# 8steps.net
KiCad netlist of a schematic drawn in EAGLE
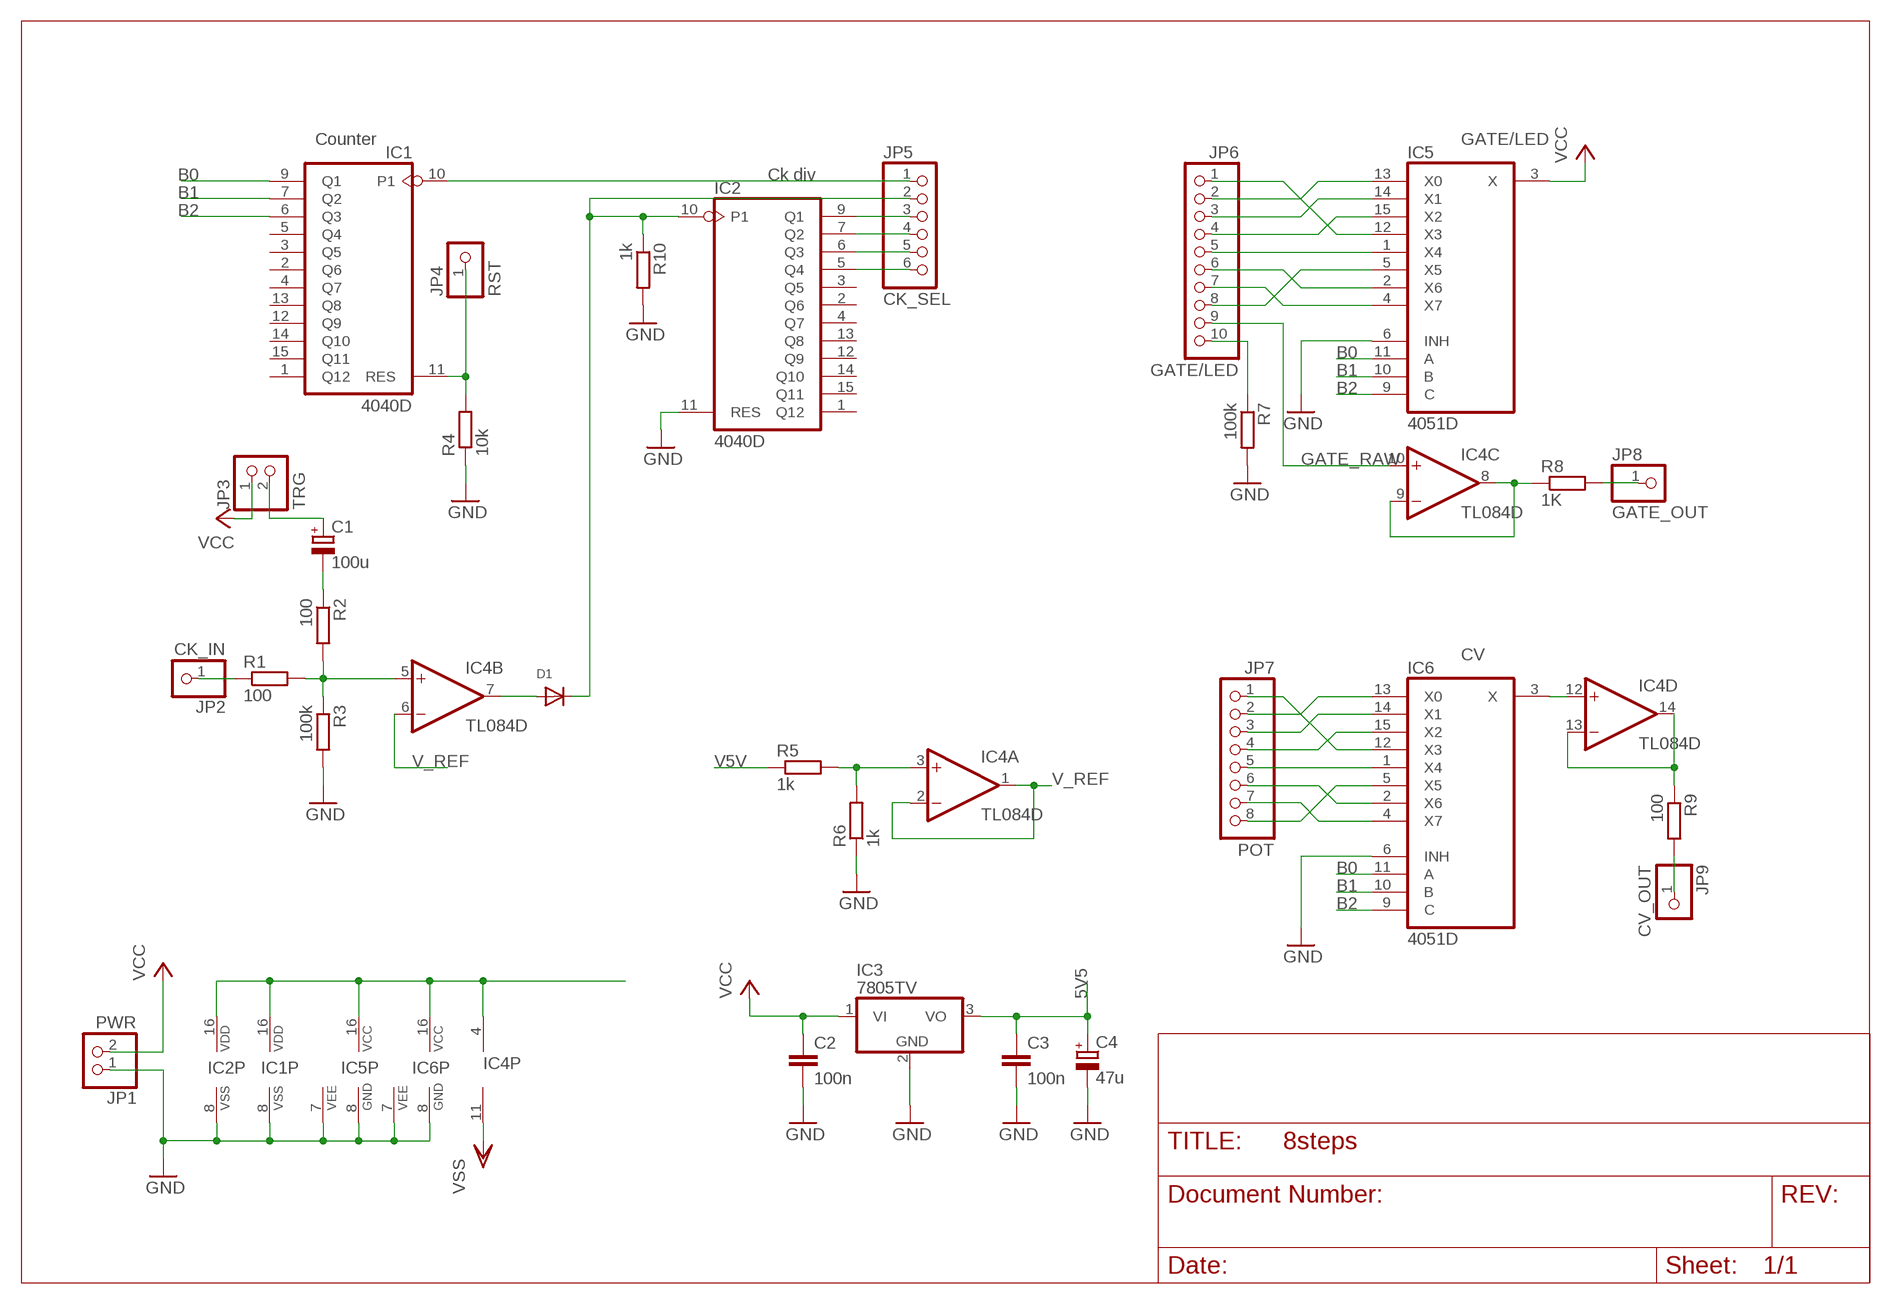
[diagram p0: schematic, sheet 1]

(export (version "E")
  (design (tool "Eeschema 10.0.6"))
  (components
    (comp (ref "C1")
      (value "100u")
      (footprint "eagle-import:E2,5-7")
      (libsource (lib "eagle-import") (part "CPOL-EUE2.5-7"))
    )
    (comp (ref "C2")
      (value "100n")
      (footprint "eagle-import:C050-025X075")
      (libsource (lib "eagle-import") (part "C-EU050-025X075"))
    )
    (comp (ref "C3")
      (value "100n")
      (footprint "eagle-import:C050-025X075")
      (libsource (lib "eagle-import") (part "C-EU050-025X075"))
    )
    (comp (ref "C4")
      (value "47u")
      (footprint "eagle-import:E2,5-7")
      (libsource (lib "eagle-import") (part "CPOL-EUE2.5-7"))
    )
    (comp (ref "D1")
      (value "DIODESOT23_WAVE")
      (footprint "eagle-import:SOT23-W")
      (libsource (lib "eagle-import") (part "DIODESOT23_WAVE"))
    )
    (comp (ref "IC1")
      (value "4040D")
      (footprint "eagle-import:SO16")
      (libsource (lib "eagle-import") (part "4040D"))
    )
    (comp (ref "IC2")
      (value "4040D")
      (footprint "eagle-import:SO16")
      (libsource (lib "eagle-import") (part "4040D"))
    )
    (comp (ref "IC3")
      (value "7805TV")
      (footprint "eagle-import:TO220V")
      (libsource (lib "eagle-import") (part "78TV05"))
    )
    (comp (ref "IC4")
      (value "TL084D")
      (footprint "eagle-import:SO14")
      (libsource (lib "eagle-import") (part "TL084D"))
    )
    (comp (ref "IC5")
      (value "4051D")
      (footprint "eagle-import:SO16")
      (libsource (lib "eagle-import") (part "4051D"))
    )
    (comp (ref "IC6")
      (value "4051D")
      (footprint "eagle-import:SO16")
      (libsource (lib "eagle-import") (part "4051D"))
    )
    (comp (ref "JP1")
      (value "PWR")
      (footprint "eagle-import:1X02")
      (libsource (lib "eagle-import") (part "PINHD-1X2"))
    )
    (comp (ref "JP2")
      (value "CK_IN")
      (footprint "eagle-import:1X01")
      (libsource (lib "eagle-import") (part "PINHD-1X1"))
    )
    (comp (ref "JP3")
      (value "TRG")
      (footprint "eagle-import:1X02")
      (libsource (lib "eagle-import") (part "PINHD-1X2"))
    )
    (comp (ref "JP4")
      (value "RST")
      (footprint "eagle-import:1X01")
      (libsource (lib "eagle-import") (part "PINHD-1X1"))
    )
    (comp (ref "JP5")
      (value "CK_SEL")
      (footprint "eagle-import:1X06")
      (libsource (lib "eagle-import") (part "PINHD-1X6"))
    )
    (comp (ref "JP6")
      (value "GATE/LED")
      (footprint "eagle-import:1X10")
      (libsource (lib "eagle-import") (part "PINHD-1X10"))
    )
    (comp (ref "JP7")
      (value "POT")
      (footprint "eagle-import:1X08")
      (libsource (lib "eagle-import") (part "PINHD-1X8"))
    )
    (comp (ref "JP8")
      (value "GATE_OUT")
      (footprint "eagle-import:1X01")
      (libsource (lib "eagle-import") (part "PINHD-1X1"))
    )
    (comp (ref "JP9")
      (value "CV_OUT")
      (footprint "eagle-import:1X01")
      (libsource (lib "eagle-import") (part "PINHD-1X1"))
    )
    (comp (ref "R1")
      (value "100")
      (footprint "eagle-import:R0805")
      (libsource (lib "eagle-import") (part "R-EU_R0805"))
    )
    (comp (ref "R2")
      (value "100")
      (footprint "eagle-import:R0805")
      (libsource (lib "eagle-import") (part "R-EU_R0805"))
    )
    (comp (ref "R3")
      (value "100k")
      (footprint "eagle-import:R0805")
      (libsource (lib "eagle-import") (part "R-EU_R0805"))
    )
    (comp (ref "R4")
      (value "10k")
      (footprint "eagle-import:R0805")
      (libsource (lib "eagle-import") (part "R-EU_R0805"))
    )
    (comp (ref "R5")
      (value "1k")
      (footprint "eagle-import:R0805")
      (libsource (lib "eagle-import") (part "R-EU_R0805"))
    )
    (comp (ref "R6")
      (value "1k")
      (footprint "eagle-import:R0805")
      (libsource (lib "eagle-import") (part "R-EU_R0805"))
    )
    (comp (ref "R7")
      (value "100k")
      (footprint "eagle-import:R0805")
      (libsource (lib "eagle-import") (part "R-EU_R0805"))
    )
    (comp (ref "R8")
      (value "1K")
      (footprint "eagle-import:R0805")
      (libsource (lib "eagle-import") (part "R-EU_R0805"))
    )
    (comp (ref "R9")
      (value "100")
      (footprint "eagle-import:R0805")
      (libsource (lib "eagle-import") (part "R-EU_R0805"))
    )
    (comp (ref "R10")
      (value "1k")
      (footprint "eagle-import:R0805")
      (libsource (lib "eagle-import") (part "R-EU_R0805"))
    )
  )
  (nets
    (net (code "1") (name "/5V5") (class "Default")
      (node (ref "C3") (pin "1") (pinfunction "1_1") (pintype "passive"))
      (node (ref "C4") (pin "+") (pinfunction "+_+") (pintype "passive"))
      (node (ref "IC3") (pin "3") (pinfunction "VO_3") (pintype "passive"))
    )
    (net (code "2") (name "/B0") (class "Default")
      (node (ref "IC1") (pin "9") (pinfunction "Q1_9") (pintype "output"))
      (node (ref "IC5") (pin "11") (pinfunction "A_11") (pintype "input"))
      (node (ref "IC6") (pin "11") (pinfunction "A_11") (pintype "input"))
    )
    (net (code "3") (name "/B1") (class "Default")
      (node (ref "IC1") (pin "7") (pinfunction "Q2_7") (pintype "output"))
      (node (ref "IC5") (pin "10") (pinfunction "B_10") (pintype "input"))
      (node (ref "IC6") (pin "10") (pinfunction "B_10") (pintype "input"))
    )
    (net (code "4") (name "/B2") (class "Default")
      (node (ref "IC1") (pin "6") (pinfunction "Q3_6") (pintype "output"))
      (node (ref "IC5") (pin "9") (pinfunction "C_9") (pintype "input"))
      (node (ref "IC6") (pin "9") (pinfunction "C_9") (pintype "input"))
    )
    (net (code "5") (name "/GATE_RAW") (class "Default")
      (node (ref "IC4") (pin "10") (pinfunction "+IN_10") (pintype "input"))
      (node (ref "JP6") (pin "9") (pinfunction "9_9") (pintype "passive"))
    )
    (net (code "6") (name "/V5V") (class "Default")
      (node (ref "IC1") (pin "16") (pinfunction "VDD_16") (pintype "power_in"))
      (node (ref "IC2") (pin "16") (pinfunction "VDD_16") (pintype "power_in"))
      (node (ref "IC4") (pin "4") (pinfunction "V+_4") (pintype "power_in"))
      (node (ref "IC5") (pin "16") (pinfunction "VCC_16") (pintype "power_in"))
      (node (ref "IC6") (pin "16") (pinfunction "VCC_16") (pintype "power_in"))
      (node (ref "R5") (pin "1") (pinfunction "1_1") (pintype "passive"))
    )
    (net (code "7") (name "/V_REF") (class "Default")
      (node (ref "IC4") (pin "1") (pinfunction "OUT_1") (pintype "output"))
      (node (ref "IC4") (pin "2") (pinfunction "-IN_2") (pintype "input"))
      (node (ref "IC4") (pin "6") (pinfunction "-IN_6") (pintype "input"))
    )
    (net (code "8") (name "GND") (class "Default")
      (node (ref "C2") (pin "2") (pinfunction "2_2") (pintype "passive"))
      (node (ref "C3") (pin "2") (pinfunction "2_2") (pintype "passive"))
      (node (ref "C4") (pin "-") (pinfunction "-_-") (pintype "passive"))
      (node (ref "IC1") (pin "8") (pinfunction "VSS_8") (pintype "power_in"))
      (node (ref "IC2") (pin "11") (pinfunction "RES_11") (pintype "input"))
      (node (ref "IC2") (pin "8") (pinfunction "VSS_8") (pintype "power_in"))
      (node (ref "IC3") (pin "2") (pinfunction "GND_2") (pintype "passive"))
      (node (ref "IC5") (pin "6") (pinfunction "INH_6") (pintype "input"))
      (node (ref "IC5") (pin "7") (pinfunction "VEE_7") (pintype "power_in"))
      (node (ref "IC5") (pin "8") (pinfunction "GND_8") (pintype "power_in"))
      (node (ref "IC6") (pin "6") (pinfunction "INH_6") (pintype "input"))
      (node (ref "IC6") (pin "7") (pinfunction "VEE_7") (pintype "power_in"))
      (node (ref "IC6") (pin "8") (pinfunction "GND_8") (pintype "power_in"))
      (node (ref "JP1") (pin "1") (pinfunction "1_1") (pintype "passive"))
      (node (ref "R10") (pin "2") (pinfunction "2_2") (pintype "passive"))
      (node (ref "R3") (pin "2") (pinfunction "2_2") (pintype "passive"))
      (node (ref "R4") (pin "1") (pinfunction "1_1") (pintype "passive"))
      (node (ref "R6") (pin "1") (pinfunction "1_1") (pintype "passive"))
      (node (ref "R7") (pin "2") (pinfunction "2_2") (pintype "passive"))
    )
    (net (code "9") (name "Net-(C1-Pad+)") (class "Default")
      (node (ref "C1") (pin "+") (pinfunction "+_+") (pintype "passive"))
      (node (ref "JP3") (pin "2") (pinfunction "2_2") (pintype "passive"))
    )
    (net (code "10") (name "Net-(C1-Pad-)") (class "Default")
      (node (ref "C1") (pin "-") (pinfunction "-_-") (pintype "passive"))
      (node (ref "R2") (pin "1") (pinfunction "1_1") (pintype "passive"))
    )
    (net (code "11") (name "Net-(D1-A)") (class "Default")
      (node (ref "D1") (pin "1") (pinfunction "A_1") (pintype "passive"))
      (node (ref "IC4") (pin "7") (pinfunction "OUT_7") (pintype "output"))
    )
    (net (code "12") (name "Net-(D1-C)") (class "Default")
      (node (ref "D1") (pin "3") (pinfunction "C_3") (pintype "passive"))
      (node (ref "IC2") (pin "10") (pinfunction "P1_10") (pintype "input"))
      (node (ref "JP5") (pin "2") (pinfunction "2_2") (pintype "passive"))
      (node (ref "R10") (pin "1") (pinfunction "1_1") (pintype "passive"))
    )
    (net (code "13") (name "Net-(IC1A-P1)") (class "Default")
      (node (ref "IC1") (pin "10") (pinfunction "P1_10") (pintype "input"))
      (node (ref "JP5") (pin "1") (pinfunction "1_1") (pintype "passive"))
    )
    (net (code "14") (name "Net-(IC1A-RES)") (class "Default")
      (node (ref "IC1") (pin "11") (pinfunction "RES_11") (pintype "input"))
      (node (ref "JP4") (pin "1") (pinfunction "1_1") (pintype "passive"))
      (node (ref "R4") (pin "2") (pinfunction "2_2") (pintype "passive"))
    )
    (net (code "15") (name "Net-(IC2A-Q1)") (class "Default")
      (node (ref "IC2") (pin "9") (pinfunction "Q1_9") (pintype "output"))
      (node (ref "JP5") (pin "3") (pinfunction "3_3") (pintype "passive"))
    )
    (net (code "16") (name "Net-(IC2A-Q2)") (class "Default")
      (node (ref "IC2") (pin "7") (pinfunction "Q2_7") (pintype "output"))
      (node (ref "JP5") (pin "4") (pinfunction "4_4") (pintype "passive"))
    )
    (net (code "17") (name "Net-(IC2A-Q3)") (class "Default")
      (node (ref "IC2") (pin "6") (pinfunction "Q3_6") (pintype "output"))
      (node (ref "JP5") (pin "5") (pinfunction "5_5") (pintype "passive"))
    )
    (net (code "18") (name "Net-(IC2A-Q4)") (class "Default")
      (node (ref "IC2") (pin "5") (pinfunction "Q4_5") (pintype "output"))
      (node (ref "JP5") (pin "6") (pinfunction "6_6") (pintype "passive"))
    )
    (net (code "19") (name "Net-(IC4A-+IN)") (class "Default")
      (node (ref "IC4") (pin "3") (pinfunction "+IN_3") (pintype "input"))
      (node (ref "R5") (pin "2") (pinfunction "2_2") (pintype "passive"))
      (node (ref "R6") (pin "2") (pinfunction "2_2") (pintype "passive"))
    )
    (net (code "20") (name "Net-(IC4B-+IN)") (class "Default")
      (node (ref "IC4") (pin "5") (pinfunction "+IN_5") (pintype "input"))
      (node (ref "R1") (pin "2") (pinfunction "2_2") (pintype "passive"))
      (node (ref "R2") (pin "2") (pinfunction "2_2") (pintype "passive"))
      (node (ref "R3") (pin "1") (pinfunction "1_1") (pintype "passive"))
    )
    (net (code "21") (name "Net-(IC4C--IN)") (class "Default")
      (node (ref "IC4") (pin "8") (pinfunction "OUT_8") (pintype "output"))
      (node (ref "IC4") (pin "9") (pinfunction "-IN_9") (pintype "input"))
      (node (ref "R8") (pin "1") (pinfunction "1_1") (pintype "passive"))
    )
    (net (code "22") (name "Net-(IC4D-+IN)") (class "Default")
      (node (ref "IC4") (pin "12") (pinfunction "+IN_12") (pintype "input"))
      (node (ref "IC6") (pin "3") (pinfunction "X_3") (pintype "bidirectional"))
    )
    (net (code "23") (name "Net-(IC4D--IN)") (class "Default")
      (node (ref "IC4") (pin "13") (pinfunction "-IN_13") (pintype "input"))
      (node (ref "IC4") (pin "14") (pinfunction "OUT_14") (pintype "output"))
      (node (ref "R9") (pin "1") (pinfunction "1_1") (pintype "passive"))
    )
    (net (code "24") (name "Net-(IC5A-X0)") (class "Default")
      (node (ref "IC5") (pin "13") (pinfunction "X0_13") (pintype "bidirectional"))
      (node (ref "JP6") (pin "2") (pinfunction "2_2") (pintype "passive"))
    )
    (net (code "25") (name "Net-(IC5A-X1)") (class "Default")
      (node (ref "IC5") (pin "14") (pinfunction "X1_14") (pintype "bidirectional"))
      (node (ref "JP6") (pin "3") (pinfunction "3_3") (pintype "passive"))
    )
    (net (code "26") (name "Net-(IC5A-X2)") (class "Default")
      (node (ref "IC5") (pin "15") (pinfunction "X2_15") (pintype "bidirectional"))
      (node (ref "JP6") (pin "4") (pinfunction "4_4") (pintype "passive"))
    )
    (net (code "27") (name "Net-(IC5A-X3)") (class "Default")
      (node (ref "IC5") (pin "12") (pinfunction "X3_12") (pintype "bidirectional"))
      (node (ref "JP6") (pin "1") (pinfunction "1_1") (pintype "passive"))
    )
    (net (code "28") (name "Net-(IC5A-X4)") (class "Default")
      (node (ref "IC5") (pin "1") (pinfunction "X4_1") (pintype "bidirectional"))
      (node (ref "JP6") (pin "5") (pinfunction "5_5") (pintype "passive"))
    )
    (net (code "29") (name "Net-(IC5A-X5)") (class "Default")
      (node (ref "IC5") (pin "5") (pinfunction "X5_5") (pintype "bidirectional"))
      (node (ref "JP6") (pin "8") (pinfunction "8_8") (pintype "passive"))
    )
    (net (code "30") (name "Net-(IC5A-X6)") (class "Default")
      (node (ref "IC5") (pin "2") (pinfunction "X6_2") (pintype "bidirectional"))
      (node (ref "JP6") (pin "6") (pinfunction "6_6") (pintype "passive"))
    )
    (net (code "31") (name "Net-(IC5A-X7)") (class "Default")
      (node (ref "IC5") (pin "4") (pinfunction "X7_4") (pintype "bidirectional"))
      (node (ref "JP6") (pin "7") (pinfunction "7_7") (pintype "passive"))
    )
    (net (code "32") (name "Net-(IC6A-X0)") (class "Default")
      (node (ref "IC6") (pin "13") (pinfunction "X0_13") (pintype "bidirectional"))
      (node (ref "JP7") (pin "2") (pinfunction "2_2") (pintype "passive"))
    )
    (net (code "33") (name "Net-(IC6A-X1)") (class "Default")
      (node (ref "IC6") (pin "14") (pinfunction "X1_14") (pintype "bidirectional"))
      (node (ref "JP7") (pin "3") (pinfunction "3_3") (pintype "passive"))
    )
    (net (code "34") (name "Net-(IC6A-X2)") (class "Default")
      (node (ref "IC6") (pin "15") (pinfunction "X2_15") (pintype "bidirectional"))
      (node (ref "JP7") (pin "4") (pinfunction "4_4") (pintype "passive"))
    )
    (net (code "35") (name "Net-(IC6A-X3)") (class "Default")
      (node (ref "IC6") (pin "12") (pinfunction "X3_12") (pintype "bidirectional"))
      (node (ref "JP7") (pin "1") (pinfunction "1_1") (pintype "passive"))
    )
    (net (code "36") (name "Net-(IC6A-X4)") (class "Default")
      (node (ref "IC6") (pin "1") (pinfunction "X4_1") (pintype "bidirectional"))
      (node (ref "JP7") (pin "5") (pinfunction "5_5") (pintype "passive"))
    )
    (net (code "37") (name "Net-(IC6A-X5)") (class "Default")
      (node (ref "IC6") (pin "5") (pinfunction "X5_5") (pintype "bidirectional"))
      (node (ref "JP7") (pin "8") (pinfunction "8_8") (pintype "passive"))
    )
    (net (code "38") (name "Net-(IC6A-X6)") (class "Default")
      (node (ref "IC6") (pin "2") (pinfunction "X6_2") (pintype "bidirectional"))
      (node (ref "JP7") (pin "6") (pinfunction "6_6") (pintype "passive"))
    )
    (net (code "39") (name "Net-(IC6A-X7)") (class "Default")
      (node (ref "IC6") (pin "4") (pinfunction "X7_4") (pintype "bidirectional"))
      (node (ref "JP7") (pin "7") (pinfunction "7_7") (pintype "passive"))
    )
    (net (code "40") (name "Net-(JP2-Pad1)") (class "Default")
      (node (ref "JP2") (pin "1") (pinfunction "1_1") (pintype "passive"))
      (node (ref "R1") (pin "1") (pinfunction "1_1") (pintype "passive"))
    )
    (net (code "41") (name "Net-(JP6-Pad10)") (class "Default")
      (node (ref "JP6") (pin "10") (pinfunction "10_10") (pintype "passive"))
      (node (ref "R7") (pin "1") (pinfunction "1_1") (pintype "passive"))
    )
    (net (code "42") (name "Net-(JP8-Pad1)") (class "Default")
      (node (ref "JP8") (pin "1") (pinfunction "1_1") (pintype "passive"))
      (node (ref "R8") (pin "2") (pinfunction "2_2") (pintype "passive"))
    )
    (net (code "43") (name "Net-(JP9-Pad1)") (class "Default")
      (node (ref "JP9") (pin "1") (pinfunction "1_1") (pintype "passive"))
      (node (ref "R9") (pin "2") (pinfunction "2_2") (pintype "passive"))
    )
    (net (code "44") (name "VCC") (class "Default")
      (node (ref "C2") (pin "1") (pinfunction "1_1") (pintype "passive"))
      (node (ref "IC3") (pin "1") (pinfunction "VI_1") (pintype "input"))
      (node (ref "IC5") (pin "3") (pinfunction "X_3") (pintype "bidirectional"))
      (node (ref "JP1") (pin "2") (pinfunction "2_2") (pintype "passive"))
      (node (ref "JP3") (pin "1") (pinfunction "1_1") (pintype "passive"))
    )
    (net (code "45") (name "VSS") (class "Default")
      (node (ref "IC4") (pin "11") (pinfunction "V-_11") (pintype "power_in"))
    )
    (net (code "46") (name "unconnected-(IC1A-Q4-Pad5)") (class "Default")
      (node (ref "IC1") (pin "5") (pinfunction "Q4_5") (pintype "output"))
    )
    (net (code "47") (name "unconnected-(IC1A-Q5-Pad3)") (class "Default")
      (node (ref "IC1") (pin "3") (pinfunction "Q5_3") (pintype "output"))
    )
    (net (code "48") (name "unconnected-(IC1A-Q6-Pad2)") (class "Default")
      (node (ref "IC1") (pin "2") (pinfunction "Q6_2") (pintype "output"))
    )
    (net (code "49") (name "unconnected-(IC1A-Q7-Pad4)") (class "Default")
      (node (ref "IC1") (pin "4") (pinfunction "Q7_4") (pintype "output"))
    )
    (net (code "50") (name "unconnected-(IC1A-Q8-Pad13)") (class "Default")
      (node (ref "IC1") (pin "13") (pinfunction "Q8_13") (pintype "output"))
    )
    (net (code "51") (name "unconnected-(IC1A-Q9-Pad12)") (class "Default")
      (node (ref "IC1") (pin "12") (pinfunction "Q9_12") (pintype "output"))
    )
    (net (code "52") (name "unconnected-(IC1A-Q10-Pad14)") (class "Default")
      (node (ref "IC1") (pin "14") (pinfunction "Q10_14") (pintype "output"))
    )
    (net (code "53") (name "unconnected-(IC1A-Q11-Pad15)") (class "Default")
      (node (ref "IC1") (pin "15") (pinfunction "Q11_15") (pintype "output"))
    )
    (net (code "54") (name "unconnected-(IC1A-Q12-Pad1)") (class "Default")
      (node (ref "IC1") (pin "1") (pinfunction "Q12_1") (pintype "output"))
    )
    (net (code "55") (name "unconnected-(IC2A-Q5-Pad3)") (class "Default")
      (node (ref "IC2") (pin "3") (pinfunction "Q5_3") (pintype "output"))
    )
    (net (code "56") (name "unconnected-(IC2A-Q6-Pad2)") (class "Default")
      (node (ref "IC2") (pin "2") (pinfunction "Q6_2") (pintype "output"))
    )
    (net (code "57") (name "unconnected-(IC2A-Q7-Pad4)") (class "Default")
      (node (ref "IC2") (pin "4") (pinfunction "Q7_4") (pintype "output"))
    )
    (net (code "58") (name "unconnected-(IC2A-Q8-Pad13)") (class "Default")
      (node (ref "IC2") (pin "13") (pinfunction "Q8_13") (pintype "output"))
    )
    (net (code "59") (name "unconnected-(IC2A-Q9-Pad12)") (class "Default")
      (node (ref "IC2") (pin "12") (pinfunction "Q9_12") (pintype "output"))
    )
    (net (code "60") (name "unconnected-(IC2A-Q10-Pad14)") (class "Default")
      (node (ref "IC2") (pin "14") (pinfunction "Q10_14") (pintype "output"))
    )
    (net (code "61") (name "unconnected-(IC2A-Q11-Pad15)") (class "Default")
      (node (ref "IC2") (pin "15") (pinfunction "Q11_15") (pintype "output"))
    )
    (net (code "62") (name "unconnected-(IC2A-Q12-Pad1)") (class "Default")
      (node (ref "IC2") (pin "1") (pinfunction "Q12_1") (pintype "output"))
    )
  )
)
